# Deserializer.net
KiCad netlist of a schematic drawn in Altium Designer
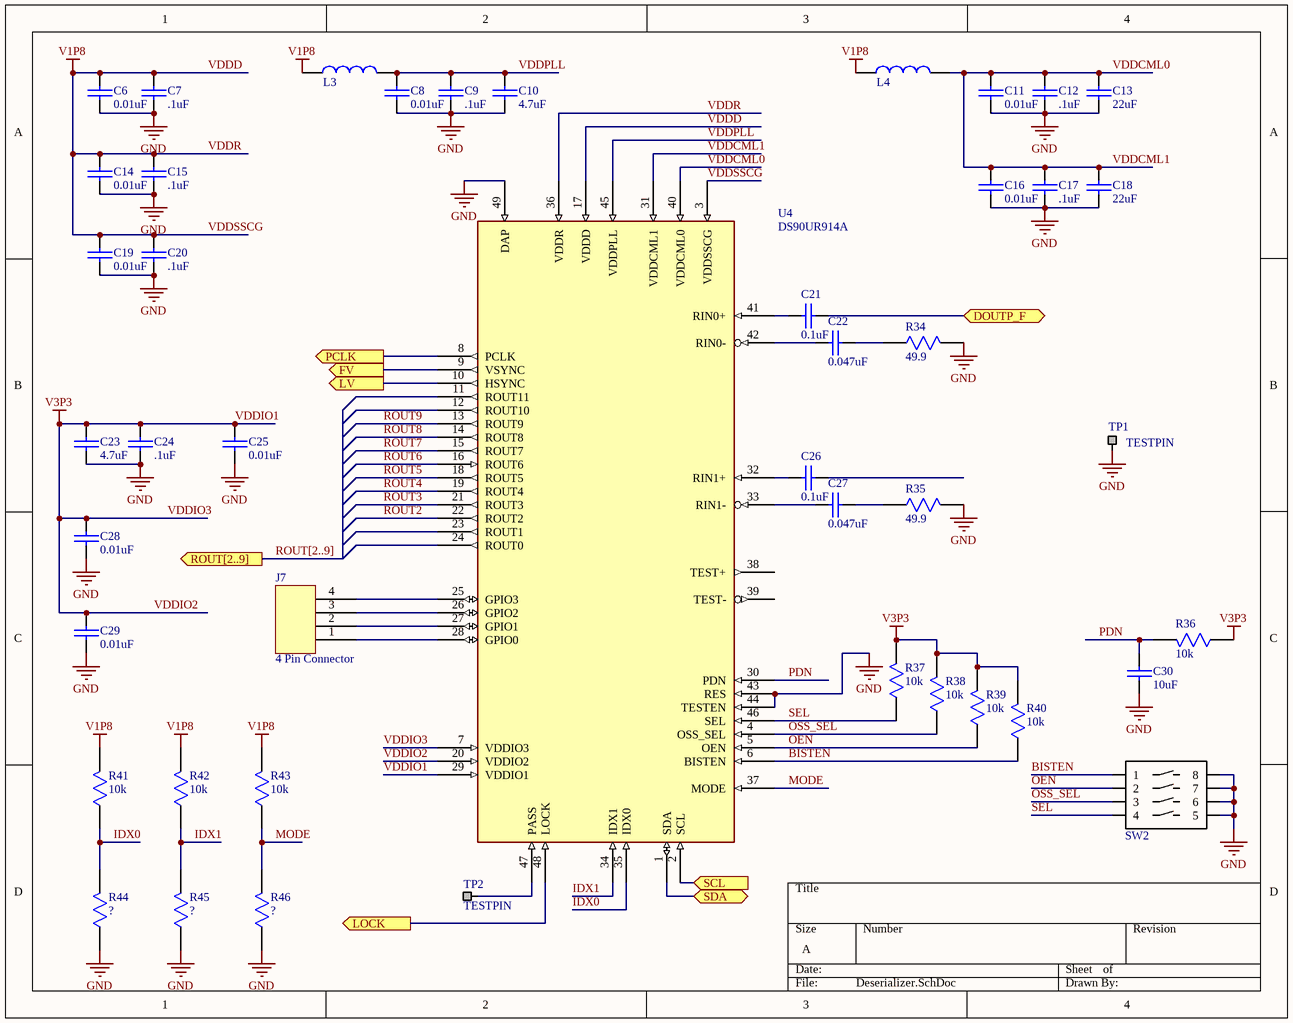
[diagram p0: Deserializer.SchDoc]

(export (version "E")
  (design (tool "Eeschema 10.0.6"))
  (components
    (comp (ref "C6")
      (value "0.01uF")
      (footprint "SMD Capacitor 0603")
      (libsource (lib "DA_Component_Library") (part "Capacitor"))
    )
    (comp (ref "C7")
      (value ".1uF")
      (footprint "SMD Capacitor 0603")
      (libsource (lib "DA_Component_Library") (part "Capacitor"))
    )
    (comp (ref "C8")
      (value "0.01uF")
      (footprint "SMD Capacitor 0603")
      (libsource (lib "DA_Component_Library") (part "Capacitor"))
    )
    (comp (ref "C9")
      (value ".1uF")
      (footprint "SMD Capacitor 0603")
      (libsource (lib "DA_Component_Library") (part "Capacitor"))
    )
    (comp (ref "C10")
      (value "4.7uF")
      (footprint "SMD Capacitor 0603")
      (libsource (lib "DA_Component_Library") (part "Capacitor"))
    )
    (comp (ref "C11")
      (value "0.01uF")
      (footprint "SMD Capacitor 0603")
      (libsource (lib "DA_Component_Library") (part "Capacitor"))
    )
    (comp (ref "C12")
      (value ".1uF")
      (footprint "SMD Capacitor 0603")
      (libsource (lib "DA_Component_Library") (part "Capacitor"))
    )
    (comp (ref "C13")
      (value "22uF")
      (footprint "SMD Capacitor 0603")
      (libsource (lib "DA_Component_Library") (part "Capacitor"))
    )
    (comp (ref "C14")
      (value "0.01uF")
      (footprint "SMD Capacitor 0603")
      (libsource (lib "DA_Component_Library") (part "Capacitor"))
    )
    (comp (ref "C15")
      (value ".1uF")
      (footprint "SMD Capacitor 0603")
      (libsource (lib "DA_Component_Library") (part "Capacitor"))
    )
    (comp (ref "C16")
      (value "0.01uF")
      (footprint "SMD Capacitor 0603")
      (libsource (lib "DA_Component_Library") (part "Capacitor"))
    )
    (comp (ref "C17")
      (value ".1uF")
      (footprint "SMD Capacitor 0603")
      (libsource (lib "DA_Component_Library") (part "Capacitor"))
    )
    (comp (ref "C18")
      (value "22uF")
      (footprint "SMD Capacitor 0603")
      (libsource (lib "DA_Component_Library") (part "Capacitor"))
    )
    (comp (ref "C19")
      (value "0.01uF")
      (footprint "SMD Capacitor 0603")
      (libsource (lib "DA_Component_Library") (part "Capacitor"))
    )
    (comp (ref "C20")
      (value ".1uF")
      (footprint "SMD Capacitor 0603")
      (libsource (lib "DA_Component_Library") (part "Capacitor"))
    )
    (comp (ref "C21")
      (value "0.1uF")
      (footprint "SMD CAP 0402")
      (libsource (lib "DA_Component_Library") (part "Capacitor"))
    )
    (comp (ref "C22")
      (value "0.047uF")
      (footprint "SMD CAP 0402")
      (libsource (lib "DA_Component_Library") (part "Capacitor"))
    )
    (comp (ref "C23")
      (value "4.7uF")
      (footprint "SMD Capacitor 0603")
      (libsource (lib "DA_Component_Library") (part "Capacitor"))
    )
    (comp (ref "C24")
      (value ".1uF")
      (footprint "SMD Capacitor 0603")
      (libsource (lib "DA_Component_Library") (part "Capacitor"))
    )
    (comp (ref "C25")
      (value "0.01uF")
      (footprint "SMD Capacitor 0603")
      (libsource (lib "DA_Component_Library") (part "Capacitor"))
    )
    (comp (ref "C26")
      (value "0.1uF")
      (footprint "SMD CAP 0402")
      (libsource (lib "DA_Component_Library") (part "Capacitor"))
    )
    (comp (ref "C27")
      (value "0.047uF")
      (footprint "SMD CAP 0402")
      (libsource (lib "DA_Component_Library") (part "Capacitor"))
    )
    (comp (ref "C28")
      (value "0.01uF")
      (footprint "SMD Capacitor 0603")
      (libsource (lib "DA_Component_Library") (part "Capacitor"))
    )
    (comp (ref "C29")
      (value "0.01uF")
      (footprint "SMD Capacitor 0603")
      (libsource (lib "DA_Component_Library") (part "Capacitor"))
    )
    (comp (ref "C30")
      (value "10uF")
      (footprint "SMD Capacitor 0603")
      (libsource (lib "DA_Component_Library") (part "Capacitor"))
    )
    (comp (ref "J7")
      (value "4 Pin Connector")
      (footprint "4Pin Verital 0.1\"")
      (libsource (lib "DA_Component_Library") (part "4 Pin Connector"))
    )
    (comp (ref "L3")
      (value "Ferrite Bead")
      (footprint "BLM18KG601SN1D")
      (libsource (lib "DA_Component_Library") (part "Ferrite Bead"))
    )
    (comp (ref "L4")
      (value "Ferrite Bead")
      (footprint "BLM18KG601SN1D")
      (libsource (lib "DA_Component_Library") (part "Ferrite Bead"))
    )
    (comp (ref "R34")
      (value "49.9")
      (footprint "SMD RES 0402")
      (libsource (lib "DA_Component_Library") (part "Resistor"))
    )
    (comp (ref "R35")
      (value "49.9")
      (footprint "SMD RES 0402")
      (libsource (lib "DA_Component_Library") (part "Resistor"))
    )
    (comp (ref "R36")
      (value "10k")
      (footprint "SMD Resistor 0603")
      (libsource (lib "DA_Component_Library") (part "Resistor"))
    )
    (comp (ref "R37")
      (value "10k")
      (footprint "SMD Resistor 0603")
      (libsource (lib "DA_Component_Library") (part "Resistor"))
    )
    (comp (ref "R38")
      (value "10k")
      (footprint "SMD Resistor 0603")
      (libsource (lib "DA_Component_Library") (part "Resistor"))
    )
    (comp (ref "R39")
      (value "10k")
      (footprint "SMD Resistor 0603")
      (libsource (lib "DA_Component_Library") (part "Resistor"))
    )
    (comp (ref "R40")
      (value "10k")
      (footprint "SMD Resistor 0603")
      (libsource (lib "DA_Component_Library") (part "Resistor"))
    )
    (comp (ref "R41")
      (value "10k")
      (footprint "SMD Resistor 0603")
      (libsource (lib "DA_Component_Library") (part "Resistor"))
    )
    (comp (ref "R42")
      (value "10k")
      (footprint "SMD Resistor 0603")
      (libsource (lib "DA_Component_Library") (part "Resistor"))
    )
    (comp (ref "R43")
      (value "10k")
      (footprint "SMD Resistor 0603")
      (libsource (lib "DA_Component_Library") (part "Resistor"))
    )
    (comp (ref "R44")
      (value "?")
      (footprint "SMD Resistor 0603")
      (libsource (lib "DA_Component_Library") (part "Resistor"))
    )
    (comp (ref "R45")
      (value "?")
      (footprint "SMD Resistor 0603")
      (libsource (lib "DA_Component_Library") (part "Resistor"))
    )
    (comp (ref "R46")
      (value "?")
      (footprint "SMD Resistor 0603")
      (libsource (lib "DA_Component_Library") (part "Resistor"))
    )
    (comp (ref "SW2")
      (value "SW_DIP_4Position")
      (footprint "218-4LPST")
      (libsource (lib "DA_Component_Library") (part "SW_DIP_4Position"))
    )
    (comp (ref "TP1")
      (value "TESTPIN")
      (footprint "TESTPIN")
      (description "TESTPIN SINGLE PIN HEADER")
      (libsource (lib "") (part "TESTPIN_1"))
    )
    (comp (ref "TP2")
      (value "TESTPIN")
      (footprint "TESTPIN")
      (description "TESTPIN SINGLE PIN HEADER")
      (libsource (lib "vh_altium_library") (part "TESTPIN"))
    )
    (comp (ref "U4")
      (value "DS90UR914A")
      (footprint "WQFN48 for DS90UB914A")
      (libsource (lib "DA_Component_Library") (part "DS90UR914A"))
    )
  )
  (nets
    (net (code "1") (name "/BISTEN") (class "Default")
      (node (ref "R40") (pin "0") (pinfunction "0_0") (pintype "passive"))
      (node (ref "SW2") (pin "1") (pinfunction "1_1") (pintype "passive"))
      (node (ref "U4") (pin "6") (pinfunction "BISTEN_6") (pintype "input"))
    )
    (net (code "2") (name "/DOUTP_F") (class "Default")
      (node (ref "C21") (pin "1") (pinfunction "1_1") (pintype "passive"))
    )
    (net (code "3") (name "/FV") (class "Default")
      (node (ref "U4") (pin "9") (pinfunction "VSYNC_9") (pintype "output"))
    )
    (net (code "4") (name "/IDX0") (class "Default")
      (node (ref "R41") (pin "0") (pinfunction "0_0") (pintype "passive"))
      (node (ref "R44") (pin "1") (pinfunction "1_1") (pintype "passive"))
      (node (ref "U4") (pin "35") (pinfunction "IDX0_35") (pintype "input"))
    )
    (net (code "5") (name "/IDX1") (class "Default")
      (node (ref "R42") (pin "0") (pinfunction "0_0") (pintype "passive"))
      (node (ref "R45") (pin "1") (pinfunction "1_1") (pintype "passive"))
      (node (ref "U4") (pin "34") (pinfunction "IDX1_34") (pintype "input"))
    )
    (net (code "6") (name "/LOCK") (class "Default")
      (node (ref "U4") (pin "48") (pinfunction "LOCK_48") (pintype "input"))
    )
    (net (code "7") (name "/LV") (class "Default")
      (node (ref "U4") (pin "10") (pinfunction "HSYNC_10") (pintype "output"))
    )
    (net (code "8") (name "/MODE") (class "Default")
      (node (ref "R43") (pin "0") (pinfunction "0_0") (pintype "passive"))
      (node (ref "R46") (pin "1") (pinfunction "1_1") (pintype "passive"))
      (node (ref "U4") (pin "37") (pinfunction "MODE_37") (pintype "input"))
    )
    (net (code "9") (name "/OEN") (class "Default")
      (node (ref "R39") (pin "0") (pinfunction "0_0") (pintype "passive"))
      (node (ref "SW2") (pin "2") (pinfunction "2_2") (pintype "passive"))
      (node (ref "U4") (pin "5") (pinfunction "OEN_5") (pintype "input"))
    )
    (net (code "10") (name "/OSS_SEL") (class "Default")
      (node (ref "R38") (pin "0") (pinfunction "0_0") (pintype "passive"))
      (node (ref "SW2") (pin "3") (pinfunction "3_3") (pintype "passive"))
      (node (ref "U4") (pin "4") (pinfunction "OSS_SEL_4") (pintype "input"))
    )
    (net (code "11") (name "/PCLK") (class "Default")
      (node (ref "U4") (pin "8") (pinfunction "PCLK_8") (pintype "output"))
    )
    (net (code "12") (name "/PDN") (class "Default")
      (node (ref "C30") (pin "0") (pinfunction "0_0") (pintype "passive"))
      (node (ref "R36") (pin "1") (pinfunction "1_1") (pintype "passive"))
      (node (ref "U4") (pin "30") (pinfunction "PDN_30") (pintype "input"))
    )
    (net (code "13") (name "/ROUT2") (class "Default")
      (node (ref "U4") (pin "22") (pinfunction "ROUT2_22") (pintype "output"))
    )
    (net (code "14") (name "/ROUT3") (class "Default")
      (node (ref "U4") (pin "21") (pinfunction "ROUT3_21") (pintype "output"))
    )
    (net (code "15") (name "/ROUT4") (class "Default")
      (node (ref "U4") (pin "19") (pinfunction "ROUT4_19") (pintype "output"))
    )
    (net (code "16") (name "/ROUT5") (class "Default")
      (node (ref "U4") (pin "18") (pinfunction "ROUT5_18") (pintype "output"))
    )
    (net (code "17") (name "/ROUT6") (class "Default")
      (node (ref "U4") (pin "16") (pinfunction "ROUT6_16") (pintype "input"))
    )
    (net (code "18") (name "/ROUT7") (class "Default")
      (node (ref "U4") (pin "15") (pinfunction "ROUT7_15") (pintype "output"))
    )
    (net (code "19") (name "/ROUT8") (class "Default")
      (node (ref "U4") (pin "14") (pinfunction "ROUT8_14") (pintype "output"))
    )
    (net (code "20") (name "/ROUT9") (class "Default")
      (node (ref "U4") (pin "13") (pinfunction "ROUT9_13") (pintype "output"))
    )
    (net (code "22") (name "/SCL") (class "Default")
      (node (ref "U4") (pin "2") (pinfunction "SCL_2") (pintype "input"))
    )
    (net (code "23") (name "/SDA") (class "Default")
      (node (ref "U4") (pin "1") (pinfunction "SDA_1") (pintype "bidirectional"))
    )
    (net (code "24") (name "/SEL") (class "Default")
      (node (ref "R37") (pin "0") (pinfunction "0_0") (pintype "passive"))
      (node (ref "SW2") (pin "4") (pinfunction "4_4") (pintype "passive"))
      (node (ref "U4") (pin "46") (pinfunction "SEL_46") (pintype "input"))
    )
    (net (code "25") (name "/VDDCML0") (class "Default")
      (node (ref "C11") (pin "0") (pinfunction "0_0") (pintype "passive"))
      (node (ref "C12") (pin "0") (pinfunction "0_0") (pintype "passive"))
      (node (ref "C13") (pin "0") (pinfunction "0_0") (pintype "passive"))
      (node (ref "C16") (pin "0") (pinfunction "0_0") (pintype "passive"))
      (node (ref "C17") (pin "0") (pinfunction "0_0") (pintype "passive"))
      (node (ref "C18") (pin "0") (pinfunction "0_0") (pintype "passive"))
      (node (ref "L4") (pin "2") (pinfunction "2_2") (pintype "passive"))
      (node (ref "U4") (pin "31") (pinfunction "VDDCML1_31") (pintype "input"))
      (node (ref "U4") (pin "40") (pinfunction "VDDCML0_40") (pintype "input"))
    )
    (net (code "26") (name "/VDDPLL") (class "Default")
      (node (ref "C10") (pin "0") (pinfunction "0_0") (pintype "passive"))
      (node (ref "C8") (pin "0") (pinfunction "0_0") (pintype "passive"))
      (node (ref "C9") (pin "0") (pinfunction "0_0") (pintype "passive"))
      (node (ref "L3") (pin "2") (pinfunction "2_2") (pintype "passive"))
      (node (ref "U4") (pin "45") (pinfunction "VDDPLL_45") (pintype "input"))
    )
    (net (code "27") (name "GND") (class "Default")
      (node (ref "C10") (pin "1") (pinfunction "1_1") (pintype "passive"))
      (node (ref "C11") (pin "1") (pinfunction "1_1") (pintype "passive"))
      (node (ref "C12") (pin "1") (pinfunction "1_1") (pintype "passive"))
      (node (ref "C13") (pin "1") (pinfunction "1_1") (pintype "passive"))
      (node (ref "C14") (pin "1") (pinfunction "1_1") (pintype "passive"))
      (node (ref "C15") (pin "1") (pinfunction "1_1") (pintype "passive"))
      (node (ref "C16") (pin "1") (pinfunction "1_1") (pintype "passive"))
      (node (ref "C17") (pin "1") (pinfunction "1_1") (pintype "passive"))
      (node (ref "C18") (pin "1") (pinfunction "1_1") (pintype "passive"))
      (node (ref "C19") (pin "1") (pinfunction "1_1") (pintype "passive"))
      (node (ref "C20") (pin "1") (pinfunction "1_1") (pintype "passive"))
      (node (ref "C23") (pin "1") (pinfunction "1_1") (pintype "passive"))
      (node (ref "C24") (pin "1") (pinfunction "1_1") (pintype "passive"))
      (node (ref "C25") (pin "1") (pinfunction "1_1") (pintype "passive"))
      (node (ref "C28") (pin "1") (pinfunction "1_1") (pintype "passive"))
      (node (ref "C29") (pin "1") (pinfunction "1_1") (pintype "passive"))
      (node (ref "C30") (pin "1") (pinfunction "1_1") (pintype "passive"))
      (node (ref "C6") (pin "1") (pinfunction "1_1") (pintype "passive"))
      (node (ref "C7") (pin "1") (pinfunction "1_1") (pintype "passive"))
      (node (ref "C8") (pin "1") (pinfunction "1_1") (pintype "passive"))
      (node (ref "C9") (pin "1") (pinfunction "1_1") (pintype "passive"))
      (node (ref "R34") (pin "1") (pinfunction "1_1") (pintype "passive"))
      (node (ref "R35") (pin "1") (pinfunction "1_1") (pintype "passive"))
      (node (ref "R44") (pin "0") (pinfunction "0_0") (pintype "passive"))
      (node (ref "R45") (pin "0") (pinfunction "0_0") (pintype "passive"))
      (node (ref "R46") (pin "0") (pinfunction "0_0") (pintype "passive"))
      (node (ref "SW2") (pin "5") (pinfunction "5_5") (pintype "passive"))
      (node (ref "SW2") (pin "6") (pinfunction "6_6") (pintype "passive"))
      (node (ref "SW2") (pin "7") (pinfunction "7_7") (pintype "passive"))
      (node (ref "SW2") (pin "8") (pinfunction "8_8") (pintype "passive"))
      (node (ref "TP1") (pin "1") (pinfunction "1_1") (pintype "passive"))
      (node (ref "U4") (pin "43") (pinfunction "RES_43") (pintype "input"))
      (node (ref "U4") (pin "44") (pinfunction "TESTEN_44") (pintype "input"))
      (node (ref "U4") (pin "49") (pinfunction "DAP_49") (pintype "input"))
    )
    (net (code "28") (name "Net-(C22-Pad1)") (class "Default")
      (node (ref "C22") (pin "1") (pinfunction "1_1") (pintype "passive"))
      (node (ref "R34") (pin "0") (pinfunction "0_0") (pintype "passive"))
    )
    (net (code "29") (name "Net-(C27-Pad1)") (class "Default")
      (node (ref "C27") (pin "1") (pinfunction "1_1") (pintype "passive"))
      (node (ref "R35") (pin "0") (pinfunction "0_0") (pintype "passive"))
    )
    (net (code "30") (name "Net-(U4-GPIO0)") (class "Default")
      (node (ref "J7") (pin "1") (pinfunction "1_1") (pintype "passive"))
      (node (ref "U4") (pin "28") (pinfunction "GPIO0_28") (pintype "bidirectional"))
    )
    (net (code "31") (name "Net-(U4-GPIO1)") (class "Default")
      (node (ref "J7") (pin "2") (pinfunction "2_2") (pintype "passive"))
      (node (ref "U4") (pin "27") (pinfunction "GPIO1_27") (pintype "bidirectional"))
    )
    (net (code "32") (name "Net-(U4-GPIO2)") (class "Default")
      (node (ref "J7") (pin "3") (pinfunction "3_3") (pintype "passive"))
      (node (ref "U4") (pin "26") (pinfunction "GPIO2_26") (pintype "bidirectional"))
    )
    (net (code "33") (name "Net-(U4-GPIO3)") (class "Default")
      (node (ref "J7") (pin "4") (pinfunction "4_4") (pintype "passive"))
      (node (ref "U4") (pin "25") (pinfunction "GPIO3_25") (pintype "bidirectional"))
    )
    (net (code "34") (name "Net-(U4-PASS)") (class "Default")
      (node (ref "TP2") (pin "1") (pinfunction "1_1") (pintype "passive"))
      (node (ref "U4") (pin "47") (pinfunction "PASS_47") (pintype "input"))
    )
    (net (code "35") (name "Net-(U4-RIN0+)") (class "Default")
      (node (ref "C21") (pin "0") (pinfunction "0_0") (pintype "passive"))
      (node (ref "U4") (pin "41") (pinfunction "RIN0+_41") (pintype "input"))
    )
    (net (code "36") (name "Net-(U4-RIN0-)") (class "Default")
      (node (ref "C22") (pin "0") (pinfunction "0_0") (pintype "passive"))
      (node (ref "U4") (pin "42") (pinfunction "RIN0-_42") (pintype "input"))
    )
    (net (code "37") (name "Net-(U4-RIN1+)") (class "Default")
      (node (ref "C26") (pin "0") (pinfunction "0_0") (pintype "passive"))
      (node (ref "U4") (pin "32") (pinfunction "RIN1+_32") (pintype "input"))
    )
    (net (code "38") (name "Net-(U4-RIN1-)") (class "Default")
      (node (ref "C27") (pin "0") (pinfunction "0_0") (pintype "passive"))
      (node (ref "U4") (pin "33") (pinfunction "RIN1-_33") (pintype "input"))
    )
    (net (code "39") (name "V1P8") (class "Default")
      (node (ref "C14") (pin "0") (pinfunction "0_0") (pintype "passive"))
      (node (ref "C15") (pin "0") (pinfunction "0_0") (pintype "passive"))
      (node (ref "C19") (pin "0") (pinfunction "0_0") (pintype "passive"))
      (node (ref "C20") (pin "0") (pinfunction "0_0") (pintype "passive"))
      (node (ref "C6") (pin "0") (pinfunction "0_0") (pintype "passive"))
      (node (ref "C7") (pin "0") (pinfunction "0_0") (pintype "passive"))
      (node (ref "L3") (pin "1") (pinfunction "1_1") (pintype "passive"))
      (node (ref "L4") (pin "1") (pinfunction "1_1") (pintype "passive"))
      (node (ref "R41") (pin "1") (pinfunction "1_1") (pintype "passive"))
      (node (ref "R42") (pin "1") (pinfunction "1_1") (pintype "passive"))
      (node (ref "R43") (pin "1") (pinfunction "1_1") (pintype "passive"))
      (node (ref "U4") (pin "17") (pinfunction "VDDD_17") (pintype "input"))
      (node (ref "U4") (pin "3") (pinfunction "VDDSSCG_3") (pintype "input"))
      (node (ref "U4") (pin "36") (pinfunction "VDDR_36") (pintype "input"))
    )
    (net (code "40") (name "V3P3") (class "Default")
      (node (ref "C23") (pin "0") (pinfunction "0_0") (pintype "passive"))
      (node (ref "C24") (pin "0") (pinfunction "0_0") (pintype "passive"))
      (node (ref "C25") (pin "0") (pinfunction "0_0") (pintype "passive"))
      (node (ref "C28") (pin "0") (pinfunction "0_0") (pintype "passive"))
      (node (ref "C29") (pin "0") (pinfunction "0_0") (pintype "passive"))
      (node (ref "R36") (pin "0") (pinfunction "0_0") (pintype "passive"))
      (node (ref "R37") (pin "1") (pinfunction "1_1") (pintype "passive"))
      (node (ref "R38") (pin "1") (pinfunction "1_1") (pintype "passive"))
      (node (ref "R39") (pin "1") (pinfunction "1_1") (pintype "passive"))
      (node (ref "R40") (pin "1") (pinfunction "1_1") (pintype "passive"))
      (node (ref "U4") (pin "20") (pinfunction "VDDIO2_20") (pintype "input"))
      (node (ref "U4") (pin "29") (pinfunction "VDDIO1_29") (pintype "input"))
      (node (ref "U4") (pin "7") (pinfunction "VDDIO3_7") (pintype "input"))
    )
    (net (code "41") (name "unconnected-(C26-Pad1)") (class "Default")
      (node (ref "C26") (pin "1") (pinfunction "1_1") (pintype "passive"))
    )
    (net (code "42") (name "unconnected-(U4-ROUT0-Pad24)") (class "Default")
      (node (ref "U4") (pin "24") (pinfunction "ROUT0_24") (pintype "output"))
    )
    (net (code "43") (name "unconnected-(U4-ROUT1-Pad23)") (class "Default")
      (node (ref "U4") (pin "23") (pinfunction "ROUT1_23") (pintype "output"))
    )
    (net (code "44") (name "unconnected-(U4-ROUT10-Pad12)") (class "Default")
      (node (ref "U4") (pin "12") (pinfunction "ROUT10_12") (pintype "output"))
    )
    (net (code "45") (name "unconnected-(U4-ROUT11-Pad11)") (class "Default")
      (node (ref "U4") (pin "11") (pinfunction "ROUT11_11") (pintype "output"))
    )
    (net (code "46") (name "unconnected-(U4-TEST+-Pad38)") (class "Default")
      (node (ref "U4") (pin "38") (pinfunction "TEST+_38") (pintype "output"))
    )
    (net (code "47") (name "unconnected-(U4-TEST--Pad39)") (class "Default")
      (node (ref "U4") (pin "39") (pinfunction "TEST-_39") (pintype "output"))
    )
  )
)
